# main.net
KiCad netlist of a schematic drawn in Altium Designer
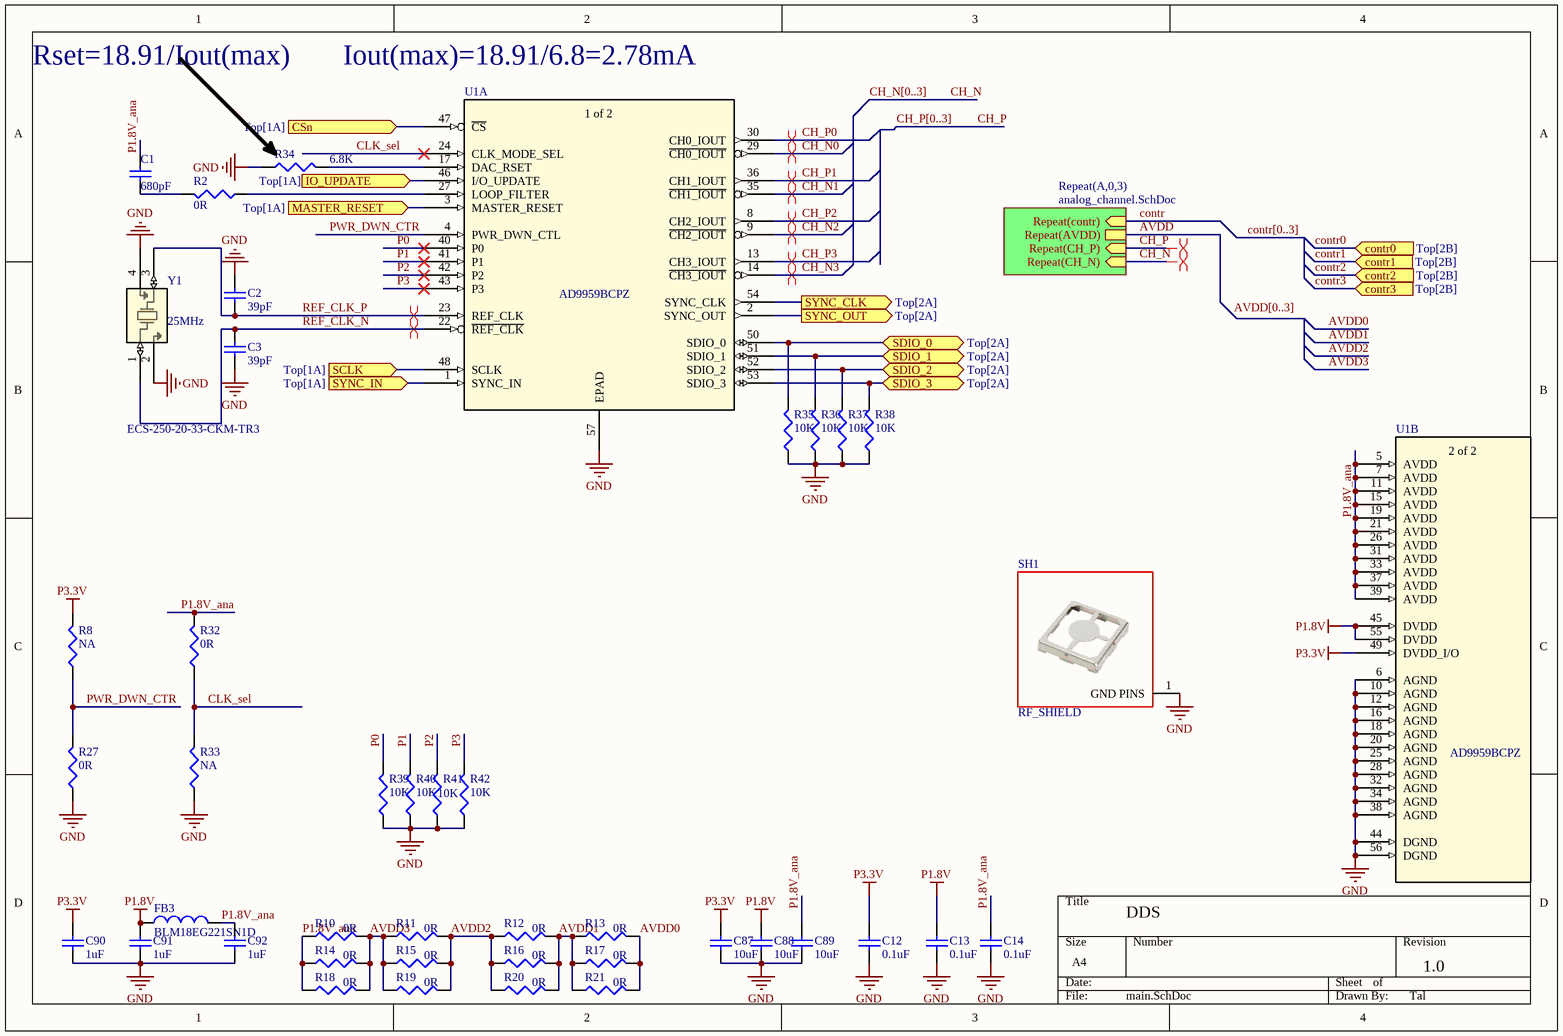
[diagram p0: main.SchDoc]

(export (version "E")
  (design (tool "Eeschema 10.0.6"))
  (components
    (comp (ref "C1")
      (value "680pF 50V")
      (footprint "C0402")
      (description "CAP CER 680PF 50V NP0 0402")
      (fields
        (field (name "MANUFACTURER PART NUMBER") "C1005C0G1H6R8D")
        (field (name "MANUFACTURER") "TDK Corporation")
        (field (name "CAPACITANCE") "680pF")
      )
      (libsource (lib "L_SCH_C") (part "CAP CER 6.8pF 50V NP0 0402"))
    )
    (comp (ref "C2")
      (value "39pF 50V")
      (footprint "C0402")
      (description "CAP CER 39PF 50V NP0 0402")
      (fields
        (field (name "MANUFACTURER PART NUMBER") "C1005C0G1H6R8D")
        (field (name "MANUFACTURER") "TDK Corporation")
        (field (name "CAPACITANCE") "39pF")
      )
      (libsource (lib "L_SCH_C") (part "CAP CER 6.8pF 50V NP0 0402"))
    )
    (comp (ref "C3")
      (value "39pF 50V")
      (footprint "C0402")
      (description "CAP CER 39PF 50V NP0 0402")
      (fields
        (field (name "MANUFACTURER PART NUMBER") "C1005C0G1H6R8D")
        (field (name "MANUFACTURER") "TDK Corporation")
        (field (name "CAPACITANCE") "39pF")
      )
      (libsource (lib "L_SCH_C") (part "CAP CER 6.8pF 50V NP0 0402"))
    )
    (comp (ref "C12")
      (value "0.1uF 50V")
      (footprint "C0402")
      (description "CAP CER 0.1uF 50V NP0 0402")
      (fields
        (field (name "MANUFACTURER PART NUMBER") "C1005C0G1H6R8D")
        (field (name "MANUFACTURER") "TDK Corporation")
        (field (name "CAPACITANCE") "0.1uF")
      )
      (libsource (lib "L_SCH_C") (part "CAP CER 6.8pF 50V NP0 0402"))
    )
    (comp (ref "C13")
      (value "0.1uF 50V")
      (footprint "C0402")
      (description "CAP CER 0.1uF 50V NP0 0402")
      (fields
        (field (name "MANUFACTURER PART NUMBER") "C1005C0G1H6R8D")
        (field (name "MANUFACTURER") "TDK Corporation")
        (field (name "CAPACITANCE") "0.1uF")
      )
      (libsource (lib "L_SCH_C") (part "CAP CER 6.8pF 50V NP0 0402"))
    )
    (comp (ref "C14")
      (value "0.1uF 50V")
      (footprint "C0402")
      (description "CAP CER 0.1uF 50V NP0 0402")
      (fields
        (field (name "MANUFACTURER PART NUMBER") "C1005C0G1H6R8D")
        (field (name "MANUFACTURER") "TDK Corporation")
        (field (name "CAPACITANCE") "0.1uF")
      )
      (libsource (lib "L_SCH_C") (part "CAP CER 6.8pF 50V NP0 0402"))
    )
    (comp (ref "C87")
      (value "10uF 10V")
      (footprint "C0402")
      (description "CAP CER 10uF 10V X5R 0402")
      (fields
        (field (name "MANUFACTURER PART NUMBER") "C1005C0G1H6R8D")
        (field (name "MANUFACTURER") "TDK Corporation")
        (field (name "CAPACITANCE") "10uF")
      )
      (libsource (lib "L_SCH_C") (part "CAP CER 6.8pF 50V NP0 0402"))
    )
    (comp (ref "C88")
      (value "10uF 10V")
      (footprint "C0402")
      (description "CAP CER 10uF 10V X5R 0402")
      (fields
        (field (name "MANUFACTURER PART NUMBER") "C1005C0G1H6R8D")
        (field (name "MANUFACTURER") "TDK Corporation")
        (field (name "CAPACITANCE") "10uF")
      )
      (libsource (lib "L_SCH_C") (part "CAP CER 6.8pF 50V NP0 0402"))
    )
    (comp (ref "C89")
      (value "10uF 10V")
      (footprint "C0402")
      (description "CAP CER 10uF 10V X5R 0402")
      (fields
        (field (name "MANUFACTURER PART NUMBER") "C1005C0G1H6R8D")
        (field (name "MANUFACTURER") "TDK Corporation")
        (field (name "CAPACITANCE") "10uF")
      )
      (libsource (lib "L_SCH_C") (part "CAP CER 6.8pF 50V NP0 0402"))
    )
    (comp (ref "C90")
      (value "1uF 25V")
      (footprint "C0402")
      (description "CAP CER 1uF 25V X5R 0402")
      (fields
        (field (name "MANUFACTURER PART NUMBER") "C1005C0G1H6R8D")
        (field (name "MANUFACTURER") "TDK Corporation")
        (field (name "CAPACITANCE") "1uF")
      )
      (libsource (lib "L_SCH_C") (part "CAP CER 6.8pF 50V NP0 0402"))
    )
    (comp (ref "C91")
      (value "1uF 25V")
      (footprint "C0402")
      (description "CAP CER 1uF 25V X5R 0402")
      (fields
        (field (name "MANUFACTURER PART NUMBER") "C1005C0G1H6R8D")
        (field (name "MANUFACTURER") "TDK Corporation")
        (field (name "CAPACITANCE") "1uF")
      )
      (libsource (lib "L_SCH_C") (part "CAP CER 6.8pF 50V NP0 0402"))
    )
    (comp (ref "C92")
      (value "1uF 25V")
      (footprint "C0402")
      (description "CAP CER 1uF 25V X5R 0402")
      (fields
        (field (name "MANUFACTURER PART NUMBER") "C1005C0G1H6R8D")
        (field (name "MANUFACTURER") "TDK Corporation")
        (field (name "CAPACITANCE") "1uF")
      )
      (libsource (lib "L_SCH_C") (part "CAP CER 6.8pF 50V NP0 0402"))
    )
    (comp (ref "FB3")
      (value "BLM18EG221SN1D")
      (footprint "fb0603")
      (description "FERRITE BEAD 220_OHM@100MHz 0603 2A 50mohm_DC")
      (fields
        (field (name "MANUFACTURER") "Taiyo Yuden")
        (field (name "MANUFACTURER PART NUMBER") "BLM18EG221SN1D")
      )
      (libsource (lib "L_SCH") (part "BK1608HS600-T"))
    )
    (comp (ref "R2")
      (value "0R")
      (footprint "R0402")
      (description "RES 0 OHM 1/10W 1% 0402 SMD")
      (fields
        (field (name "MANUFACTURER PART NUMBER") "ERJ-2RKF1000X")
        (field (name "MANUFACTURER") "Panasonic Electronic Components")
      )
      (libsource (lib "L_SCH_R") (part "RES 100 OHM 1/10W 1% 0402 SMD"))
    )
    (comp (ref "R8")
      (value "NA")
      (footprint "R0402")
      (description "RES 0 OHM 1/10W 1% 0402 SMD")
      (fields
        (field (name "MANUFACTURER PART NUMBER") "ERJ-2RKF1000X")
        (field (name "MANUFACTURER") "Panasonic Electronic Components")
      )
      (libsource (lib "L_SCH_R") (part "RES 100 OHM 1/10W 1% 0402 SMD"))
    )
    (comp (ref "R10")
      (value "0R")
      (footprint "R0805")
      (description "RES 0 OHM 1/8W 1% 0805 SMD")
      (fields
        (field (name "MANUFACTURER PART NUMBER") "RMCF0805FT200R")
        (field (name "MANUFACTURER") "Stackpole Electronics Inc")
      )
      (libsource (lib "L_SCH_R") (part "RES 200 OHM 1/8W 1% 0805 SMD"))
    )
    (comp (ref "R11")
      (value "0R")
      (footprint "R0805")
      (description "RES 0 OHM 1/8W 1% 0805 SMD")
      (fields
        (field (name "MANUFACTURER PART NUMBER") "RMCF0805FT200R")
        (field (name "MANUFACTURER") "Stackpole Electronics Inc")
      )
      (libsource (lib "L_SCH_R") (part "RES 200 OHM 1/8W 1% 0805 SMD"))
    )
    (comp (ref "R12")
      (value "0R")
      (footprint "R0805")
      (description "RES 0 OHM 1/8W 1% 0805 SMD")
      (fields
        (field (name "MANUFACTURER PART NUMBER") "RMCF0805FT200R")
        (field (name "MANUFACTURER") "Stackpole Electronics Inc")
      )
      (libsource (lib "L_SCH_R") (part "RES 200 OHM 1/8W 1% 0805 SMD"))
    )
    (comp (ref "R13")
      (value "0R")
      (footprint "R0805")
      (description "RES 0 OHM 1/8W 1% 0805 SMD")
      (fields
        (field (name "MANUFACTURER PART NUMBER") "RMCF0805FT200R")
        (field (name "MANUFACTURER") "Stackpole Electronics Inc")
      )
      (libsource (lib "L_SCH_R") (part "RES 200 OHM 1/8W 1% 0805 SMD"))
    )
    (comp (ref "R14")
      (value "0R")
      (footprint "R0805")
      (description "RES 0 OHM 1/8W 1% 0805 SMD")
      (fields
        (field (name "MANUFACTURER PART NUMBER") "RMCF0805FT200R")
        (field (name "MANUFACTURER") "Stackpole Electronics Inc")
      )
      (libsource (lib "L_SCH_R") (part "RES 200 OHM 1/8W 1% 0805 SMD"))
    )
    (comp (ref "R15")
      (value "0R")
      (footprint "R0805")
      (description "RES 0 OHM 1/8W 1% 0805 SMD")
      (fields
        (field (name "MANUFACTURER PART NUMBER") "RMCF0805FT200R")
        (field (name "MANUFACTURER") "Stackpole Electronics Inc")
      )
      (libsource (lib "L_SCH_R") (part "RES 200 OHM 1/8W 1% 0805 SMD"))
    )
    (comp (ref "R16")
      (value "0R")
      (footprint "R0805")
      (description "RES 0 OHM 1/8W 1% 0805 SMD")
      (fields
        (field (name "MANUFACTURER PART NUMBER") "RMCF0805FT200R")
        (field (name "MANUFACTURER") "Stackpole Electronics Inc")
      )
      (libsource (lib "L_SCH_R") (part "RES 200 OHM 1/8W 1% 0805 SMD"))
    )
    (comp (ref "R17")
      (value "0R")
      (footprint "R0805")
      (description "RES 0 OHM 1/8W 1% 0805 SMD")
      (fields
        (field (name "MANUFACTURER PART NUMBER") "RMCF0805FT200R")
        (field (name "MANUFACTURER") "Stackpole Electronics Inc")
      )
      (libsource (lib "L_SCH_R") (part "RES 200 OHM 1/8W 1% 0805 SMD"))
    )
    (comp (ref "R18")
      (value "0R")
      (footprint "R0805")
      (description "RES 0 OHM 1/8W 1% 0805 SMD")
      (fields
        (field (name "MANUFACTURER PART NUMBER") "RMCF0805FT200R")
        (field (name "MANUFACTURER") "Stackpole Electronics Inc")
      )
      (libsource (lib "L_SCH_R") (part "RES 200 OHM 1/8W 1% 0805 SMD"))
    )
    (comp (ref "R19")
      (value "0R")
      (footprint "R0805")
      (description "RES 0 OHM 1/8W 1% 0805 SMD")
      (fields
        (field (name "MANUFACTURER PART NUMBER") "RMCF0805FT200R")
        (field (name "MANUFACTURER") "Stackpole Electronics Inc")
      )
      (libsource (lib "L_SCH_R") (part "RES 200 OHM 1/8W 1% 0805 SMD"))
    )
    (comp (ref "R20")
      (value "0R")
      (footprint "R0805")
      (description "RES 0 OHM 1/8W 1% 0805 SMD")
      (fields
        (field (name "MANUFACTURER PART NUMBER") "RMCF0805FT200R")
        (field (name "MANUFACTURER") "Stackpole Electronics Inc")
      )
      (libsource (lib "L_SCH_R") (part "RES 200 OHM 1/8W 1% 0805 SMD"))
    )
    (comp (ref "R21")
      (value "0R")
      (footprint "R0805")
      (description "RES 0 OHM 1/8W 1% 0805 SMD")
      (fields
        (field (name "MANUFACTURER PART NUMBER") "RMCF0805FT200R")
        (field (name "MANUFACTURER") "Stackpole Electronics Inc")
      )
      (libsource (lib "L_SCH_R") (part "RES 200 OHM 1/8W 1% 0805 SMD"))
    )
    (comp (ref "R27")
      (value "0R")
      (footprint "R0402")
      (description "RES 0 OHM 1/10W 1% 0402 SMD")
      (fields
        (field (name "MANUFACTURER PART NUMBER") "ERJ-2RKF1000X")
        (field (name "MANUFACTURER") "Panasonic Electronic Components")
      )
      (libsource (lib "L_SCH_R") (part "RES 100 OHM 1/10W 1% 0402 SMD"))
    )
    (comp (ref "R32")
      (value "0R")
      (footprint "R0402")
      (description "RES 0 OHM 1/10W 1% 0402 SMD")
      (fields
        (field (name "MANUFACTURER PART NUMBER") "ERJ-2RKF1000X")
        (field (name "MANUFACTURER") "Panasonic Electronic Components")
      )
      (libsource (lib "L_SCH_R") (part "RES 100 OHM 1/10W 1% 0402 SMD"))
    )
    (comp (ref "R33")
      (value "NA")
      (footprint "R0402")
      (description "RES 0 OHM 1/10W 1% 0402 SMD")
      (fields
        (field (name "MANUFACTURER PART NUMBER") "ERJ-2RKF1000X")
        (field (name "MANUFACTURER") "Panasonic Electronic Components")
      )
      (libsource (lib "L_SCH_R") (part "RES 100 OHM 1/10W 1% 0402 SMD"))
    )
    (comp (ref "R34")
      (value "6.8K")
      (footprint "R0402")
      (description "RES 6.8K OHM 1/16W 1% 0402")
      (fields
        (field (name "MANUFACTURER PART NUMBER") "RMCF0402FT3K09")
        (field (name "MANUFACTURER") "Stackpole Electronics Inc")
      )
      (libsource (lib "L_SCH_R") (part "RES 3.09K OHM 1/16W 1% 0402"))
    )
    (comp (ref "R35")
      (value "10K")
      (footprint "R0402")
      (description "RES 10K OHM 1/16W 1% 0402")
      (fields
        (field (name "MANUFACTURER PART NUMBER") "RMCF0402FT3K09")
        (field (name "MANUFACTURER") "Stackpole Electronics Inc")
      )
      (libsource (lib "L_SCH_R") (part "RES 3.09K OHM 1/16W 1% 0402"))
    )
    (comp (ref "R36")
      (value "10K")
      (footprint "R0402")
      (description "RES 10K OHM 1/16W 1% 0402")
      (fields
        (field (name "MANUFACTURER PART NUMBER") "RMCF0402FT3K09")
        (field (name "MANUFACTURER") "Stackpole Electronics Inc")
      )
      (libsource (lib "L_SCH_R") (part "RES 3.09K OHM 1/16W 1% 0402"))
    )
    (comp (ref "R37")
      (value "10K")
      (footprint "R0402")
      (description "RES 10K OHM 1/16W 1% 0402")
      (fields
        (field (name "MANUFACTURER PART NUMBER") "RMCF0402FT3K09")
        (field (name "MANUFACTURER") "Stackpole Electronics Inc")
      )
      (libsource (lib "L_SCH_R") (part "RES 3.09K OHM 1/16W 1% 0402"))
    )
    (comp (ref "R38")
      (value "10K")
      (footprint "R0402")
      (description "RES 10K OHM 1/16W 1% 0402")
      (fields
        (field (name "MANUFACTURER PART NUMBER") "RMCF0402FT3K09")
        (field (name "MANUFACTURER") "Stackpole Electronics Inc")
      )
      (libsource (lib "L_SCH_R") (part "RES 3.09K OHM 1/16W 1% 0402"))
    )
    (comp (ref "R39")
      (value "10K")
      (footprint "R0402")
      (description "RES 10K OHM 1/16W 1% 0402")
      (fields
        (field (name "MANUFACTURER PART NUMBER") "RMCF0402FT3K09")
        (field (name "MANUFACTURER") "Stackpole Electronics Inc")
      )
      (libsource (lib "L_SCH_R") (part "RES 3.09K OHM 1/16W 1% 0402"))
    )
    (comp (ref "R40")
      (value "10K")
      (footprint "R0402")
      (description "RES 10K OHM 1/16W 1% 0402")
      (fields
        (field (name "MANUFACTURER PART NUMBER") "RMCF0402FT3K09")
        (field (name "MANUFACTURER") "Stackpole Electronics Inc")
      )
      (libsource (lib "L_SCH_R") (part "RES 3.09K OHM 1/16W 1% 0402"))
    )
    (comp (ref "R41")
      (value "10K")
      (footprint "R0402")
      (description "RES 10K OHM 1/16W 1% 0402")
      (fields
        (field (name "MANUFACTURER PART NUMBER") "RMCF0402FT3K09")
        (field (name "MANUFACTURER") "Stackpole Electronics Inc")
      )
      (libsource (lib "L_SCH_R") (part "RES 3.09K OHM 1/16W 1% 0402"))
    )
    (comp (ref "R42")
      (value "10K")
      (footprint "R0402")
      (description "RES 10K OHM 1/16W 1% 0402")
      (fields
        (field (name "MANUFACTURER PART NUMBER") "RMCF0402FT3K09")
        (field (name "MANUFACTURER") "Stackpole Electronics Inc")
      )
      (libsource (lib "L_SCH_R") (part "RES 3.09K OHM 1/16W 1% 0402"))
    )
    (comp (ref "SH1")
      (value "RF_SHIELD")
      (footprint "SMS201F")
      (description "RF SHIELD 0.5\" X 0.538\" SMD")
      (fields
        (field (name "MANUFACTURER_PART_NUMBER") "SMS-201F")
        (field (name "MANUFACTURER") "Leader Tech Inc.")
      )
      (libsource (lib "DDS_PCB_1") (part "RF_SHIELD"))
    )
    (comp (ref "U1")
      (value "AD9959BCPZ")
      (footprint "CP_56_1_ADI")
      (description "No Description Available")
      (fields (field (name "COPYRIGHT") "Copyright (C) 2023 Ultra Librarian. All rights reserved."))
      (libsource (lib "") (part "AD9959BCPZ_1"))
    )
    (comp (ref "Y1")
      (value "ECS-250-20-33-CKM-TR3")
      (footprint "SMD4_ECX-32_3p2x2p5_ECS")
      (description "No Description Available")
      (fields (field (name "COPYRIGHT") "Copyright (C) 2023 Ultra Librarian. All rights reserved."))
      (libsource (lib "ECS-250-20-33-CKM-TR3") (part "ECS-250-20-33-CKM-TR3"))
    )
  )
  (nets
    (net (code "2") (name "/AVDD0") (class "Default")
      (node (ref "R13") (pin "2") (pinfunction "2_2") (pintype "passive"))
      (node (ref "R17") (pin "2") (pinfunction "2_2") (pintype "passive"))
      (node (ref "R21") (pin "2") (pinfunction "2_2") (pintype "passive"))
    )
    (net (code "3") (name "/AVDD1") (class "Default")
      (node (ref "R12") (pin "2") (pinfunction "2_2") (pintype "passive"))
      (node (ref "R13") (pin "1") (pinfunction "1_1") (pintype "passive"))
      (node (ref "R16") (pin "2") (pinfunction "2_2") (pintype "passive"))
      (node (ref "R17") (pin "1") (pinfunction "1_1") (pintype "passive"))
      (node (ref "R20") (pin "2") (pinfunction "2_2") (pintype "passive"))
      (node (ref "R21") (pin "1") (pinfunction "1_1") (pintype "passive"))
    )
    (net (code "4") (name "/AVDD2") (class "Default")
      (node (ref "R11") (pin "2") (pinfunction "2_2") (pintype "passive"))
      (node (ref "R12") (pin "1") (pinfunction "1_1") (pintype "passive"))
      (node (ref "R15") (pin "2") (pinfunction "2_2") (pintype "passive"))
      (node (ref "R16") (pin "1") (pinfunction "1_1") (pintype "passive"))
      (node (ref "R19") (pin "2") (pinfunction "2_2") (pintype "passive"))
      (node (ref "R20") (pin "1") (pinfunction "1_1") (pintype "passive"))
    )
    (net (code "5") (name "/AVDD3") (class "Default")
      (node (ref "R10") (pin "2") (pinfunction "2_2") (pintype "passive"))
      (node (ref "R11") (pin "1") (pinfunction "1_1") (pintype "passive"))
      (node (ref "R14") (pin "2") (pinfunction "2_2") (pintype "passive"))
      (node (ref "R15") (pin "1") (pinfunction "1_1") (pintype "passive"))
      (node (ref "R18") (pin "2") (pinfunction "2_2") (pintype "passive"))
      (node (ref "R19") (pin "1") (pinfunction "1_1") (pintype "passive"))
    )
    (net (code "8") (name "/CH_N0") (class "Default")
      (node (ref "U1") (pin "29") (pinfunction "~{CH0_IOUT}_29") (pintype "output"))
    )
    (net (code "9") (name "/CH_N1") (class "Default")
      (node (ref "U1") (pin "35") (pinfunction "~{CH1_IOUT}_35") (pintype "output"))
    )
    (net (code "10") (name "/CH_N2") (class "Default")
      (node (ref "U1") (pin "9") (pinfunction "~{CH2_IOUT}_9") (pintype "output"))
    )
    (net (code "11") (name "/CH_N3") (class "Default")
      (node (ref "U1") (pin "14") (pinfunction "~{CH3_IOUT}_14") (pintype "output"))
    )
    (net (code "14") (name "/CH_P0") (class "Default")
      (node (ref "U1") (pin "30") (pinfunction "CH0_IOUT_30") (pintype "output"))
    )
    (net (code "15") (name "/CH_P1") (class "Default")
      (node (ref "U1") (pin "36") (pinfunction "CH1_IOUT_36") (pintype "output"))
    )
    (net (code "16") (name "/CH_P2") (class "Default")
      (node (ref "U1") (pin "8") (pinfunction "CH2_IOUT_8") (pintype "output"))
    )
    (net (code "17") (name "/CH_P3") (class "Default")
      (node (ref "U1") (pin "13") (pinfunction "CH3_IOUT_13") (pintype "output"))
    )
    (net (code "19") (name "/CLK_sel") (class "Default")
      (node (ref "R32") (pin "1") (pinfunction "1_1") (pintype "passive"))
      (node (ref "R33") (pin "2") (pinfunction "2_2") (pintype "passive"))
      (node (ref "U1") (pin "24") (pinfunction "CLK_MODE_SEL_24") (pintype "input"))
    )
    (net (code "20") (name "/CSn") (class "Default")
      (node (ref "U1") (pin "47") (pinfunction "~{CS}_47") (pintype "input"))
    )
    (net (code "21") (name "/IO_UPDATE") (class "Default")
      (node (ref "U1") (pin "46") (pinfunction "I/O_UPDATE_46") (pintype "input"))
    )
    (net (code "22") (name "/MASTER_RESET") (class "Default")
      (node (ref "U1") (pin "3") (pinfunction "MASTER_RESET_3") (pintype "input"))
    )
    (net (code "23") (name "/P0") (class "Default")
      (node (ref "R39") (pin "2") (pinfunction "2_2") (pintype "passive"))
      (node (ref "U1") (pin "40") (pinfunction "P0_40") (pintype "input"))
    )
    (net (code "24") (name "/P1") (class "Default")
      (node (ref "R40") (pin "2") (pinfunction "2_2") (pintype "passive"))
      (node (ref "U1") (pin "41") (pinfunction "P1_41") (pintype "input"))
    )
    (net (code "25") (name "/P1.8V_ana") (class "Default")
      (node (ref "C1") (pin "1") (pinfunction "1_1") (pintype "passive"))
      (node (ref "C14") (pin "2") (pinfunction "2_2") (pintype "passive"))
      (node (ref "C89") (pin "2") (pinfunction "2_2") (pintype "passive"))
      (node (ref "C92") (pin "2") (pinfunction "2_2") (pintype "passive"))
      (node (ref "FB3") (pin "2") (pinfunction "2_2") (pintype "passive"))
      (node (ref "R10") (pin "1") (pinfunction "1_1") (pintype "passive"))
      (node (ref "R14") (pin "1") (pinfunction "1_1") (pintype "passive"))
      (node (ref "R18") (pin "1") (pinfunction "1_1") (pintype "passive"))
      (node (ref "R32") (pin "2") (pinfunction "2_2") (pintype "passive"))
      (node (ref "U1") (pin "11") (pinfunction "AVDD_11") (pintype "input"))
      (node (ref "U1") (pin "15") (pinfunction "AVDD_15") (pintype "input"))
      (node (ref "U1") (pin "19") (pinfunction "AVDD_19") (pintype "input"))
      (node (ref "U1") (pin "21") (pinfunction "AVDD_21") (pintype "input"))
      (node (ref "U1") (pin "26") (pinfunction "AVDD_26") (pintype "input"))
      (node (ref "U1") (pin "31") (pinfunction "AVDD_31") (pintype "input"))
      (node (ref "U1") (pin "33") (pinfunction "AVDD_33") (pintype "input"))
      (node (ref "U1") (pin "37") (pinfunction "AVDD_37") (pintype "input"))
      (node (ref "U1") (pin "39") (pinfunction "AVDD_39") (pintype "input"))
      (node (ref "U1") (pin "5") (pinfunction "AVDD_5") (pintype "input"))
      (node (ref "U1") (pin "7") (pinfunction "AVDD_7") (pintype "input"))
    )
    (net (code "26") (name "/P2") (class "Default")
      (node (ref "R41") (pin "2") (pinfunction "2_2") (pintype "passive"))
      (node (ref "U1") (pin "42") (pinfunction "P2_42") (pintype "input"))
    )
    (net (code "27") (name "/P3") (class "Default")
      (node (ref "R42") (pin "2") (pinfunction "2_2") (pintype "passive"))
      (node (ref "U1") (pin "43") (pinfunction "P3_43") (pintype "input"))
    )
    (net (code "28") (name "/PWR_DWN_CTR") (class "Default")
      (node (ref "R27") (pin "2") (pinfunction "2_2") (pintype "passive"))
      (node (ref "R8") (pin "1") (pinfunction "1_1") (pintype "passive"))
      (node (ref "U1") (pin "4") (pinfunction "PWR_DWN_CTL_4") (pintype "input"))
    )
    (net (code "29") (name "/REF_CLK_N") (class "Default")
      (node (ref "C3") (pin "2") (pinfunction "2_2") (pintype "passive"))
      (node (ref "U1") (pin "22") (pinfunction "~{REF_CLK}_22") (pintype "input"))
      (node (ref "Y1") (pin "1") (pinfunction "1_1") (pintype "bidirectional"))
    )
    (net (code "30") (name "/REF_CLK_P") (class "Default")
      (node (ref "C2") (pin "1") (pinfunction "1_1") (pintype "passive"))
      (node (ref "U1") (pin "23") (pinfunction "REF_CLK_23") (pintype "input"))
      (node (ref "Y1") (pin "3") (pinfunction "3_3") (pintype "bidirectional"))
    )
    (net (code "31") (name "/SCLK") (class "Default")
      (node (ref "U1") (pin "48") (pinfunction "SCLK_48") (pintype "input"))
    )
    (net (code "32") (name "/SDIO_0") (class "Default")
      (node (ref "R35") (pin "2") (pinfunction "2_2") (pintype "passive"))
      (node (ref "U1") (pin "50") (pinfunction "SDIO_0_50") (pintype "bidirectional"))
    )
    (net (code "33") (name "/SDIO_1") (class "Default")
      (node (ref "R36") (pin "2") (pinfunction "2_2") (pintype "passive"))
      (node (ref "U1") (pin "51") (pinfunction "SDIO_1_51") (pintype "bidirectional"))
    )
    (net (code "34") (name "/SDIO_2") (class "Default")
      (node (ref "R37") (pin "2") (pinfunction "2_2") (pintype "passive"))
      (node (ref "U1") (pin "52") (pinfunction "SDIO_2_52") (pintype "bidirectional"))
    )
    (net (code "35") (name "/SDIO_3") (class "Default")
      (node (ref "R38") (pin "2") (pinfunction "2_2") (pintype "passive"))
      (node (ref "U1") (pin "53") (pinfunction "SDIO_3_53") (pintype "bidirectional"))
    )
    (net (code "36") (name "/SYNC_CLK") (class "Default")
      (node (ref "U1") (pin "54") (pinfunction "SYNC_CLK_54") (pintype "output"))
    )
    (net (code "37") (name "/SYNC_IN") (class "Default")
      (node (ref "U1") (pin "1") (pinfunction "SYNC_IN_1") (pintype "input"))
    )
    (net (code "38") (name "/SYNC_OUT") (class "Default")
      (node (ref "U1") (pin "2") (pinfunction "SYNC_OUT_2") (pintype "output"))
    )
    (net (code "45") (name "GND") (class "Default")
      (node (ref "C12") (pin "1") (pinfunction "1_1") (pintype "passive"))
      (node (ref "C13") (pin "1") (pinfunction "1_1") (pintype "passive"))
      (node (ref "C14") (pin "1") (pinfunction "1_1") (pintype "passive"))
      (node (ref "C2") (pin "2") (pinfunction "2_2") (pintype "passive"))
      (node (ref "C3") (pin "1") (pinfunction "1_1") (pintype "passive"))
      (node (ref "C87") (pin "1") (pinfunction "1_1") (pintype "passive"))
      (node (ref "C88") (pin "1") (pinfunction "1_1") (pintype "passive"))
      (node (ref "C89") (pin "1") (pinfunction "1_1") (pintype "passive"))
      (node (ref "C90") (pin "1") (pinfunction "1_1") (pintype "passive"))
      (node (ref "C91") (pin "1") (pinfunction "1_1") (pintype "passive"))
      (node (ref "C92") (pin "1") (pinfunction "1_1") (pintype "passive"))
      (node (ref "R27") (pin "1") (pinfunction "1_1") (pintype "passive"))
      (node (ref "R33") (pin "1") (pinfunction "1_1") (pintype "passive"))
      (node (ref "R34") (pin "1") (pinfunction "1_1") (pintype "passive"))
      (node (ref "R35") (pin "1") (pinfunction "1_1") (pintype "passive"))
      (node (ref "R36") (pin "1") (pinfunction "1_1") (pintype "passive"))
      (node (ref "R37") (pin "1") (pinfunction "1_1") (pintype "passive"))
      (node (ref "R38") (pin "1") (pinfunction "1_1") (pintype "passive"))
      (node (ref "R39") (pin "1") (pinfunction "1_1") (pintype "passive"))
      (node (ref "R40") (pin "1") (pinfunction "1_1") (pintype "passive"))
      (node (ref "R41") (pin "1") (pinfunction "1_1") (pintype "passive"))
      (node (ref "R42") (pin "1") (pinfunction "1_1") (pintype "passive"))
      (node (ref "SH1") (pin "1") (pinfunction "GND_PINS_1") (pintype "passive"))
      (node (ref "U1") (pin "10") (pinfunction "AGND_10") (pintype "input"))
      (node (ref "U1") (pin "12") (pinfunction "AGND_12") (pintype "input"))
      (node (ref "U1") (pin "16") (pinfunction "AGND_16") (pintype "input"))
      (node (ref "U1") (pin "18") (pinfunction "AGND_18") (pintype "input"))
      (node (ref "U1") (pin "20") (pinfunction "AGND_20") (pintype "input"))
      (node (ref "U1") (pin "25") (pinfunction "AGND_25") (pintype "input"))
      (node (ref "U1") (pin "28") (pinfunction "AGND_28") (pintype "input"))
      (node (ref "U1") (pin "32") (pinfunction "AGND_32") (pintype "input"))
      (node (ref "U1") (pin "34") (pinfunction "AGND_34") (pintype "input"))
      (node (ref "U1") (pin "38") (pinfunction "AGND_38") (pintype "input"))
      (node (ref "U1") (pin "44") (pinfunction "DGND_44") (pintype "input"))
      (node (ref "U1") (pin "56") (pinfunction "DGND_56") (pintype "input"))
      (node (ref "U1") (pin "57") (pinfunction "EPAD_57") (pintype "passive"))
      (node (ref "U1") (pin "6") (pinfunction "AGND_6") (pintype "input"))
      (node (ref "Y1") (pin "2") (pinfunction "2_2") (pintype "passive"))
      (node (ref "Y1") (pin "4") (pinfunction "4_4") (pintype "passive"))
    )
    (net (code "46") (name "Net-(C1-Pad2)") (class "Default")
      (node (ref "C1") (pin "2") (pinfunction "2_2") (pintype "passive"))
      (node (ref "R2") (pin "2") (pinfunction "2_2") (pintype "passive"))
    )
    (net (code "47") (name "Net-(U1A-DAC_RSET)") (class "Default")
      (node (ref "R34") (pin "2") (pinfunction "2_2") (pintype "passive"))
      (node (ref "U1") (pin "17") (pinfunction "DAC_RSET_17") (pintype "input"))
    )
    (net (code "48") (name "Net-(U1A-LOOP_FILTER)") (class "Default")
      (node (ref "R2") (pin "1") (pinfunction "1_1") (pintype "passive"))
      (node (ref "U1") (pin "27") (pinfunction "LOOP_FILTER_27") (pintype "input"))
    )
    (net (code "49") (name "P1.8V") (class "Default")
      (node (ref "C13") (pin "2") (pinfunction "2_2") (pintype "passive"))
      (node (ref "C88") (pin "2") (pinfunction "2_2") (pintype "passive"))
      (node (ref "C91") (pin "2") (pinfunction "2_2") (pintype "passive"))
      (node (ref "FB3") (pin "1") (pinfunction "1_1") (pintype "passive"))
      (node (ref "U1") (pin "45") (pinfunction "DVDD_45") (pintype "input"))
      (node (ref "U1") (pin "55") (pinfunction "DVDD_55") (pintype "input"))
    )
    (net (code "50") (name "P3.3V") (class "Default")
      (node (ref "C12") (pin "2") (pinfunction "2_2") (pintype "passive"))
      (node (ref "C87") (pin "2") (pinfunction "2_2") (pintype "passive"))
      (node (ref "C90") (pin "2") (pinfunction "2_2") (pintype "passive"))
      (node (ref "R8") (pin "2") (pinfunction "2_2") (pintype "passive"))
      (node (ref "U1") (pin "49") (pinfunction "DVDD_I/O_49") (pintype "input"))
    )
  )
)
